# PWR_Supply.net
KiCad netlist of a schematic drawn in Altium Designer
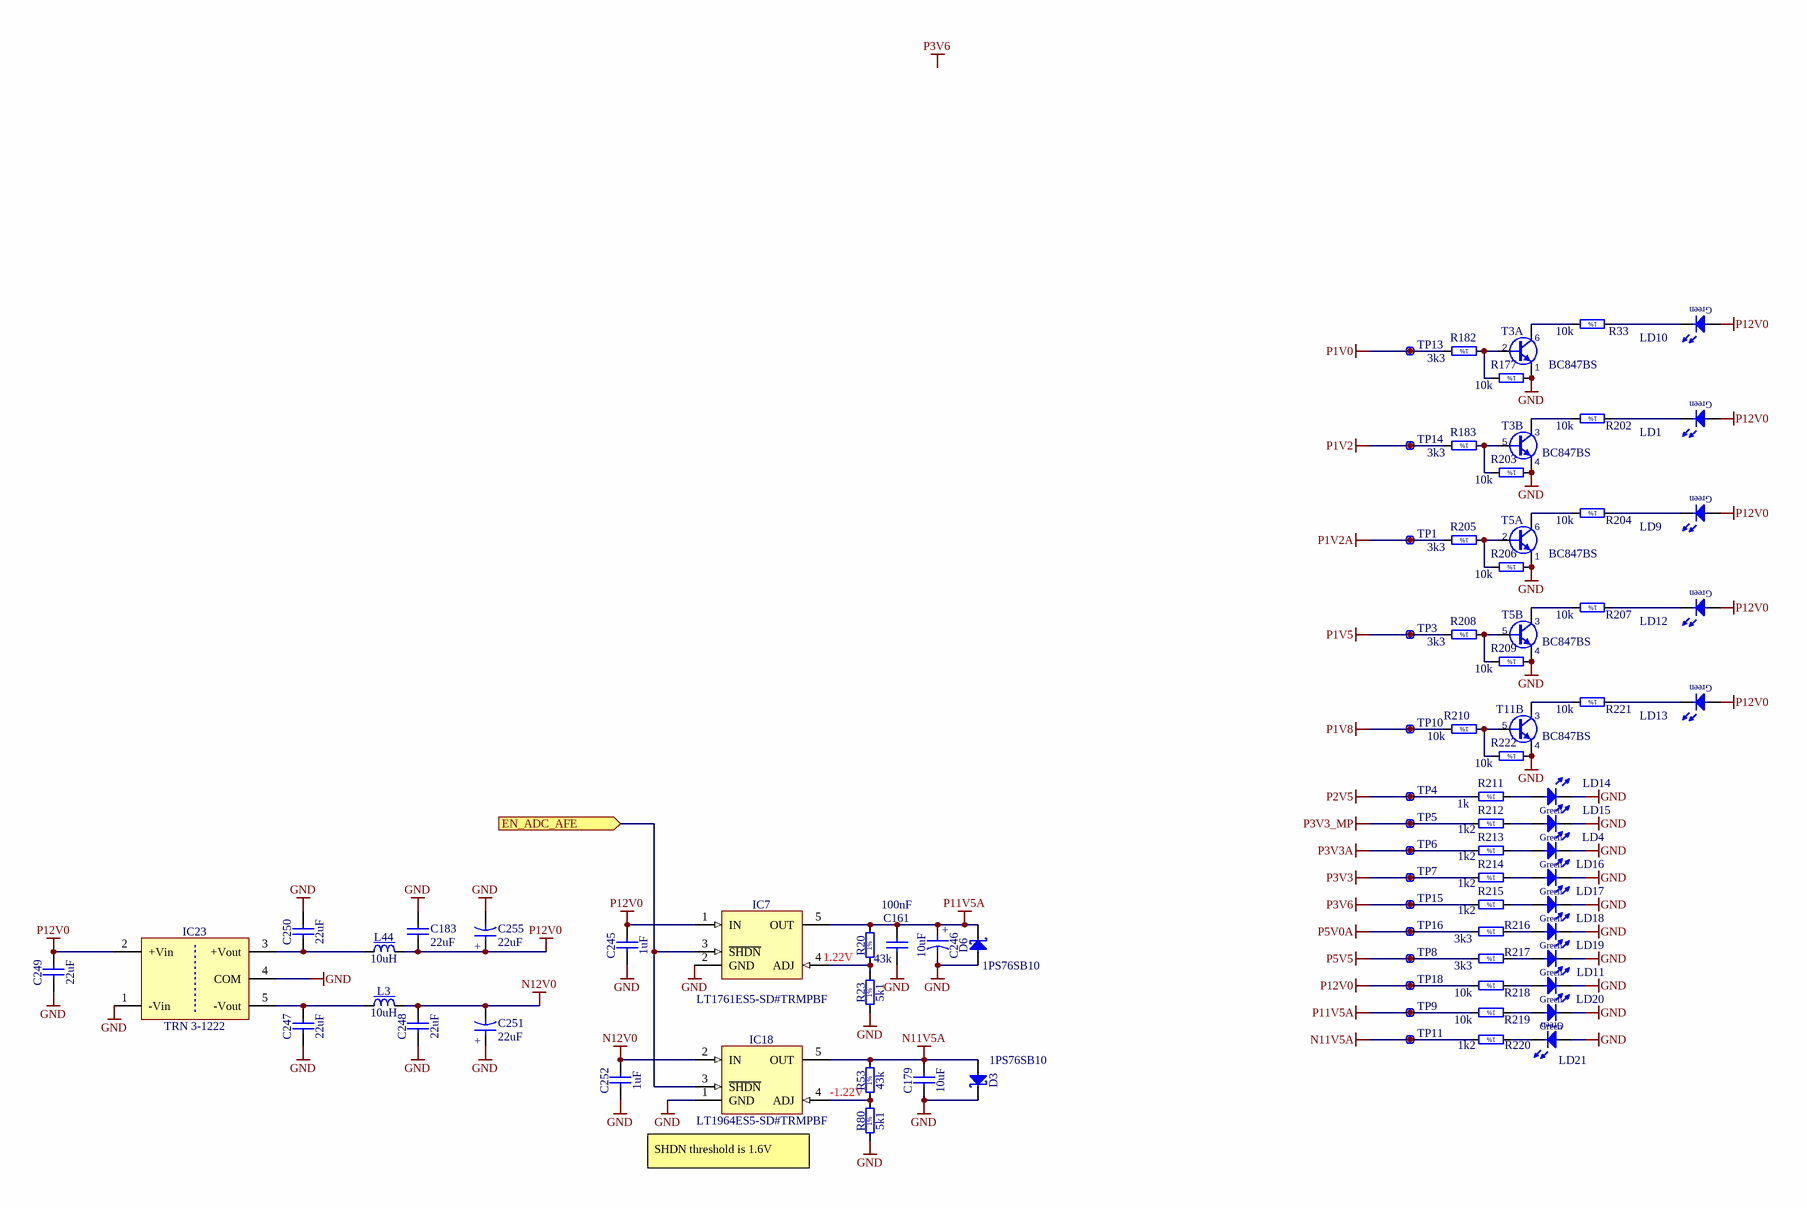
[diagram p0: PWR_Supply.SchDoc]

(export (version "E")
  (design (tool "Eeschema 10.0.6"))
  (components
    (comp (ref "C161")
      (value "100nF")
      (footprint "CAPC1005X55N")
      (description "Non-polarised capacitor")
      (fields
        (field (name "PART NUMBER") "CC0402_100NF_16V_10%_X5R")
        (field (name "VOLTAGE") "16V")
        (field (name "AUTHOR") "CERN DEM JLC")
      )
      (libsource (lib "Capacitors") (part "Capacitor - non polarized"))
    )
    (comp (ref "C179")
      (value "10uF")
      (footprint "CAPC2012X135N")
      (description "Non-polarised capacitor")
      (fields
        (field (name "PART NUMBER") "CC0805_10UF_16V_10%_X5R")
        (field (name "VOLTAGE") "16V")
        (field (name "AUTHOR") "CERN DEM JLC")
      )
      (libsource (lib "Capacitors") (part "Capacitor - non polarized"))
    )
    (comp (ref "C183")
      (value "22uF")
      (footprint "CAPC2012X135N")
      (description "Non-polarised capacitor")
      (fields
        (field (name "PART NUMBER") "CC0805_22UF_16V_10%_X5R")
        (field (name "VOLTAGE") "16V")
        (field (name "AUTHOR") "CERN DEM JLC")
      )
      (libsource (lib "Capacitors") (part "Capacitor - non polarized"))
    )
    (comp (ref "C245")
      (value "1uF")
      (footprint "CAPC1608X87N")
      (description "Non-polarised capacitor")
      (fields
        (field (name "PART NUMBER") "CC0603_1UF_25V_10%_X7R")
        (field (name "VOLTAGE") "25V")
        (field (name "AUTHOR") "CERN DEM JLC")
      )
      (libsource (lib "Capacitors") (part "Capacitor - non polarized"))
    )
    (comp (ref "C246")
      (value "10uF")
      (footprint "CAPMP3216X180N")
      (description "Polarised capacitor")
      (fields
        (field (name "PART NUMBER") "CTE3216-18_10UF_16V_20%_AVX_TCJ")
        (field (name "VOLTAGE") "16V")
        (field (name "AUTHOR") "CERN DEM JLC")
      )
      (libsource (lib "Capacitors") (part "Capacitor - polarized"))
    )
    (comp (ref "C247")
      (value "22uF")
      (footprint "CAPC2012X135N")
      (description "Non-polarised capacitor")
      (fields
        (field (name "PART NUMBER") "CC0805_22UF_16V_10%_X5R")
        (field (name "VOLTAGE") "16V")
        (field (name "AUTHOR") "CERN DEM JLC")
      )
      (libsource (lib "Capacitors") (part "Capacitor - non polarized"))
    )
    (comp (ref "C248")
      (value "22uF")
      (footprint "CAPC2012X135N")
      (description "Non-polarised capacitor")
      (fields
        (field (name "PART NUMBER") "CC0805_22UF_16V_10%_X5R")
        (field (name "VOLTAGE") "16V")
        (field (name "AUTHOR") "CERN DEM JLC")
      )
      (libsource (lib "Capacitors") (part "Capacitor - non polarized"))
    )
    (comp (ref "C249")
      (value "22uF")
      (footprint "CAPC2012X135N")
      (description "Non-polarised capacitor")
      (fields
        (field (name "PART NUMBER") "CC0805_22UF_16V_10%_X5R")
        (field (name "VOLTAGE") "16V")
        (field (name "AUTHOR") "CERN DEM JLC")
      )
      (libsource (lib "Capacitors") (part "Capacitor - non polarized"))
    )
    (comp (ref "C250")
      (value "22uF")
      (footprint "CAPC2012X135N")
      (description "Non-polarised capacitor")
      (fields
        (field (name "PART NUMBER") "CC0805_22UF_16V_10%_X5R")
        (field (name "VOLTAGE") "16V")
        (field (name "AUTHOR") "CERN DEM JLC")
      )
      (libsource (lib "Capacitors") (part "Capacitor - non polarized"))
    )
    (comp (ref "C251")
      (value "22uF")
      (footprint "CAPMP3528X210N")
      (description "Polarised capacitor")
      (fields
        (field (name "PART NUMBER") "CTE3528-21_22UF_10V_10%_LESR0700")
        (field (name "VOLTAGE") "10V")
        (field (name "AUTHOR") "CERN DEM JLC")
      )
      (libsource (lib "Capacitors") (part "Capacitor - polarized"))
    )
    (comp (ref "C252")
      (value "1uF")
      (footprint "CAPC1608X87N")
      (description "Non-polarised capacitor")
      (fields
        (field (name "PART NUMBER") "CC0603_1UF_25V_10%_X7R")
        (field (name "VOLTAGE") "25V")
        (field (name "AUTHOR") "CERN DEM JLC")
      )
      (libsource (lib "Capacitors") (part "Capacitor - non polarized"))
    )
    (comp (ref "C255")
      (value "22uF")
      (footprint "CAPMP3528X210N")
      (description "Polarised capacitor")
      (fields
        (field (name "PART NUMBER") "CTE3528-21_22UF_10V_10%_LESR0700")
        (field (name "VOLTAGE") "10V")
        (field (name "AUTHOR") "CERN DEM JLC")
      )
      (libsource (lib "Capacitors") (part "Capacitor - polarized"))
    )
    (comp (ref "D3")
      (value "1PS76SB10")
      (footprint "SOD2512X110N")
      (description "Schottky Diode")
      (fields
        (field (name "VOLTAGE") "30V")
        (field (name "POWER") "200mA")
        (field (name "AUTHOR") "CERN DEM JLC")
      )
      (libsource (lib "ICs And Semiconductors") (part "Diode Schottky"))
    )
    (comp (ref "D6")
      (value "1PS76SB10")
      (footprint "SOD2512X110N")
      (description "Schottky Diode")
      (fields
        (field (name "VOLTAGE") "30V")
        (field (name "POWER") "200mA")
        (field (name "AUTHOR") "CERN DEM JLC")
      )
      (libsource (lib "ICs And Semiconductors") (part "Diode Schottky"))
    )
    (comp (ref "IC7")
      (value "LT1761ES5-SD#TRMPBF")
      (footprint "SOT95P280X100-5N")
      (description "100mA, Low Noise, LDO Micropower Adjustable Regulator in SOT-23")
      (fields (field (name "MANUFACTURER") "LINEAR TECHNOLOGY") (field (name "AUTHOR") "CERN DEM JLC"))
      (libsource (lib "ICs And Semiconductors") (part "LT1761-SD"))
    )
    (comp (ref "IC18")
      (value "LT1964ES5-SD#TRMPBF")
      (footprint "SOT95P280X100-5N")
      (description "200mA, Low Noise, Low Dropout Negative Micropower Regulator")
      (fields (field (name "MANUFACTURER") "LINEAR TECHNOLOGY") (field (name "AUTHOR") "CERN DEM JLC"))
      (libsource (lib "ICs And Semiconductors") (part "LT1964-SD"))
    )
    (comp (ref "IC23")
      (value "TRN 3-1222")
      (footprint "DCDC_TRACO_TRN3")
      (description "TRACO, TRN 3 Serie, Dual Output DCDC Converter")
      (fields (field (name "MANUFACTURER") "TRACO POWER") (field (name "AUTHOR") "CERN DEM JLC"))
      (libsource (lib "ICs And Semiconductors") (part "DCDC_TRACO_TRN3_Dual Output"))
    )
    (comp (ref "L3")
      (value "10uH")
      (footprint "IND_MURATA-PS_8400")
      (description "Inductor With Core")
      (fields
        (field (name "PART NUMBER") "IND_10UH_10%_MURATA-PS_8400")
        (field (name "POWER") "950mA")
        (field (name "AUTHOR") "CERN DEM JLC")
      )
      (libsource (lib "Inductors & Transformers") (part "Inductor With Magnetic core"))
    )
    (comp (ref "L44")
      (value "10uH")
      (footprint "IND_MURATA-PS_8400")
      (description "Inductor With Core")
      (fields
        (field (name "PART NUMBER") "IND_10UH_10%_MURATA-PS_8400")
        (field (name "POWER") "950mA")
        (field (name "AUTHOR") "CERN DEM JLC")
      )
      (libsource (lib "Inductors & Transformers") (part "Inductor With Magnetic core"))
    )
    (comp (ref "LD1")
      (value "Green")
      (footprint "LED_KINGBRIGHT_KPH-1608CGCKr")
      (description "Green 0603")
      (fields
        (field (name "PART NUMBER") "LED_KINGBRIGHT_KPH-1608CGCK")
        (field (name "MANUFACTURER") "KINGBRIGHT")
        (field (name "AUTHOR") "CERN DEM JLC")
      )
      (libsource (lib "LIBRARY_SCH") (part "LED_0603_Green"))
    )
    (comp (ref "LD4")
      (value "Green")
      (footprint "LED_KINGBRIGHT_KPH-1608CGCKr")
      (description "Green 0603")
      (fields
        (field (name "PART NUMBER") "LED_KINGBRIGHT_KPH-1608CGCK")
        (field (name "MANUFACTURER") "KINGBRIGHT")
        (field (name "AUTHOR") "CERN DEM JLC")
      )
      (libsource (lib "LIBRARY_SCH") (part "LED_0603_Green"))
    )
    (comp (ref "LD9")
      (value "Green")
      (footprint "LED_KINGBRIGHT_KPH-1608CGCKr")
      (description "Green 0603")
      (fields
        (field (name "PART NUMBER") "LED_KINGBRIGHT_KPH-1608CGCK")
        (field (name "MANUFACTURER") "KINGBRIGHT")
        (field (name "AUTHOR") "CERN DEM JLC")
      )
      (libsource (lib "LIBRARY_SCH") (part "LED_0603_Green"))
    )
    (comp (ref "LD10")
      (value "Green")
      (footprint "LED_KINGBRIGHT_KPH-1608CGCKr")
      (description "Green 0603")
      (fields
        (field (name "PART NUMBER") "LED_KINGBRIGHT_KPH-1608CGCK")
        (field (name "MANUFACTURER") "KINGBRIGHT")
        (field (name "AUTHOR") "CERN DEM JLC")
      )
      (libsource (lib "LIBRARY_SCH") (part "LED_0603_Green"))
    )
    (comp (ref "LD11")
      (value "Green")
      (footprint "LED_KINGBRIGHT_KPH-1608CGCKr")
      (description "Green 0603")
      (fields
        (field (name "PART NUMBER") "LED_KINGBRIGHT_KPH-1608CGCK")
        (field (name "MANUFACTURER") "KINGBRIGHT")
        (field (name "AUTHOR") "CERN DEM JLC")
      )
      (libsource (lib "LIBRARY_SCH") (part "LED_0603_Green"))
    )
    (comp (ref "LD12")
      (value "Green")
      (footprint "LED_KINGBRIGHT_KPH-1608CGCKr")
      (description "Green 0603")
      (fields
        (field (name "PART NUMBER") "LED_KINGBRIGHT_KPH-1608CGCK")
        (field (name "MANUFACTURER") "KINGBRIGHT")
        (field (name "AUTHOR") "CERN DEM JLC")
      )
      (libsource (lib "LIBRARY_SCH") (part "LED_0603_Green"))
    )
    (comp (ref "LD13")
      (value "Green")
      (footprint "LED_KINGBRIGHT_KPH-1608CGCKr")
      (description "Green 0603")
      (fields
        (field (name "PART NUMBER") "LED_KINGBRIGHT_KPH-1608CGCK")
        (field (name "MANUFACTURER") "KINGBRIGHT")
        (field (name "AUTHOR") "CERN DEM JLC")
      )
      (libsource (lib "LIBRARY_SCH") (part "LED_0603_Green"))
    )
    (comp (ref "LD14")
      (value "Green")
      (footprint "LED_KINGBRIGHT_KPH-1608CGCKr")
      (description "Green 0603")
      (fields
        (field (name "PART NUMBER") "LED_KINGBRIGHT_KPH-1608CGCK")
        (field (name "MANUFACTURER") "KINGBRIGHT")
        (field (name "AUTHOR") "CERN DEM JLC")
      )
      (libsource (lib "LIBRARY_SCH") (part "LED_0603_Green"))
    )
    (comp (ref "LD15")
      (value "Green")
      (footprint "LED_KINGBRIGHT_KPH-1608CGCKr")
      (description "Green 0603")
      (fields
        (field (name "PART NUMBER") "LED_KINGBRIGHT_KPH-1608CGCK")
        (field (name "MANUFACTURER") "KINGBRIGHT")
        (field (name "AUTHOR") "CERN DEM JLC")
      )
      (libsource (lib "LIBRARY_SCH") (part "LED_0603_Green"))
    )
    (comp (ref "LD16")
      (value "Green")
      (footprint "LED_KINGBRIGHT_KPH-1608CGCKr")
      (description "Green 0603")
      (fields
        (field (name "PART NUMBER") "LED_KINGBRIGHT_KPH-1608CGCK")
        (field (name "MANUFACTURER") "KINGBRIGHT")
        (field (name "AUTHOR") "CERN DEM JLC")
      )
      (libsource (lib "LIBRARY_SCH") (part "LED_0603_Green"))
    )
    (comp (ref "LD17")
      (value "Green")
      (footprint "LED_KINGBRIGHT_KPH-1608CGCKr")
      (description "Green 0603")
      (fields
        (field (name "PART NUMBER") "LED_KINGBRIGHT_KPH-1608CGCK")
        (field (name "MANUFACTURER") "KINGBRIGHT")
        (field (name "AUTHOR") "CERN DEM JLC")
      )
      (libsource (lib "LIBRARY_SCH") (part "LED_0603_Green"))
    )
    (comp (ref "LD18")
      (value "Green")
      (footprint "LED_KINGBRIGHT_KPH-1608CGCKr")
      (description "Green 0603")
      (fields
        (field (name "PART NUMBER") "LED_KINGBRIGHT_KPH-1608CGCK")
        (field (name "MANUFACTURER") "KINGBRIGHT")
        (field (name "AUTHOR") "CERN DEM JLC")
      )
      (libsource (lib "LIBRARY_SCH") (part "LED_0603_Green"))
    )
    (comp (ref "LD19")
      (value "Green")
      (footprint "LED_KINGBRIGHT_KPH-1608CGCKr")
      (description "Green 0603")
      (fields
        (field (name "PART NUMBER") "LED_KINGBRIGHT_KPH-1608CGCK")
        (field (name "MANUFACTURER") "KINGBRIGHT")
        (field (name "AUTHOR") "CERN DEM JLC")
      )
      (libsource (lib "LIBRARY_SCH") (part "LED_0603_Green"))
    )
    (comp (ref "LD20")
      (value "Green")
      (footprint "LED_KINGBRIGHT_KPH-1608CGCKr")
      (description "Green 0603")
      (fields
        (field (name "PART NUMBER") "LED_KINGBRIGHT_KPH-1608CGCK")
        (field (name "MANUFACTURER") "KINGBRIGHT")
        (field (name "AUTHOR") "CERN DEM JLC")
      )
      (libsource (lib "LIBRARY_SCH") (part "LED_0603_Green"))
    )
    (comp (ref "LD21")
      (value "Green")
      (footprint "LED_KINGBRIGHT_KPH-1608CGCKr")
      (description "Green 0603")
      (fields
        (field (name "PART NUMBER") "LED_KINGBRIGHT_KPH-1608CGCK")
        (field (name "MANUFACTURER") "KINGBRIGHT")
        (field (name "AUTHOR") "CERN DEM JLC")
      )
      (libsource (lib "LIBRARY_SCH") (part "LED_0603_Green"))
    )
    (comp (ref "R20")
      (value "43k")
      (footprint "RESC1005X40N")
      (description "Resistor - 1%")
      (fields
        (field (name "PART NUMBER") "R0402_43K_1%_0.0625W_100PPM")
        (field (name "POWER") "0.0625W")
        (field (name "AUTHOR") "CERN DEM JLC")
      )
      (libsource (lib "Resistors") (part "Resistor - 1%"))
    )
    (comp (ref "R23")
      (value "5k1")
      (footprint "RESC1005X40N")
      (description "Resistor - 1%")
      (fields
        (field (name "PART NUMBER") "R0402_5K1_1%_0.0625W_100PPM")
        (field (name "POWER") "0.0625W")
        (field (name "AUTHOR") "CERN DEM JLC")
      )
      (libsource (lib "Resistors") (part "Resistor - 1%"))
    )
    (comp (ref "R33")
      (value "10k")
      (footprint "RESC1005X40N")
      (description "Resistor - 1%")
      (fields
        (field (name "PART NUMBER") "R0402_10K_1%_0.0625W_100PPM")
        (field (name "POWER") "0.0625W")
        (field (name "AUTHOR") "CERN DEM JLC")
      )
      (libsource (lib "Resistors") (part "Resistor - 1%"))
    )
    (comp (ref "R53")
      (value "43k")
      (footprint "RESC1005X40N")
      (description "Resistor - 1%")
      (fields
        (field (name "PART NUMBER") "R0402_43K_1%_0.0625W_100PPM")
        (field (name "POWER") "0.0625W")
        (field (name "AUTHOR") "CERN DEM JLC")
      )
      (libsource (lib "Resistors") (part "Resistor - 1%"))
    )
    (comp (ref "R80")
      (value "5k1")
      (footprint "RESC1005X40N")
      (description "Resistor - 1%")
      (fields
        (field (name "PART NUMBER") "R0402_5K1_1%_0.0625W_100PPM")
        (field (name "POWER") "0.0625W")
        (field (name "AUTHOR") "CERN DEM JLC")
      )
      (libsource (lib "Resistors") (part "Resistor - 1%"))
    )
    (comp (ref "R177")
      (value "10k")
      (footprint "RESC1005X40N")
      (description "Resistor - 1%")
      (fields
        (field (name "PART NUMBER") "R0402_10K_1%_0.0625W_100PPM")
        (field (name "POWER") "0.0625W")
        (field (name "AUTHOR") "CERN DEM JLC")
      )
      (libsource (lib "Resistors") (part "Resistor - 1%"))
    )
    (comp (ref "R182")
      (value "3k3")
      (footprint "RESC1608X55N")
      (description "Resistor - 1%")
      (fields
        (field (name "PART NUMBER") "R0603_3K3_1%_0.1W_100PPM")
        (field (name "POWER") "0.1W")
        (field (name "AUTHOR") "CERN DEM JLC")
      )
      (libsource (lib "Resistors") (part "Resistor - 1%"))
    )
    (comp (ref "R183")
      (value "3k3")
      (footprint "RESC1608X55N")
      (description "Resistor - 1%")
      (fields
        (field (name "PART NUMBER") "R0603_3K3_1%_0.1W_100PPM")
        (field (name "POWER") "0.1W")
        (field (name "AUTHOR") "CERN DEM JLC")
      )
      (libsource (lib "Resistors") (part "Resistor - 1%"))
    )
    (comp (ref "R202")
      (value "10k")
      (footprint "RESC1005X40N")
      (description "Resistor - 1%")
      (fields
        (field (name "PART NUMBER") "R0402_10K_1%_0.0625W_100PPM")
        (field (name "POWER") "0.0625W")
        (field (name "AUTHOR") "CERN DEM JLC")
      )
      (libsource (lib "Resistors") (part "Resistor - 1%"))
    )
    (comp (ref "R203")
      (value "10k")
      (footprint "RESC1005X40N")
      (description "Resistor - 1%")
      (fields
        (field (name "PART NUMBER") "R0402_10K_1%_0.0625W_100PPM")
        (field (name "POWER") "0.0625W")
        (field (name "AUTHOR") "CERN DEM JLC")
      )
      (libsource (lib "Resistors") (part "Resistor - 1%"))
    )
    (comp (ref "R204")
      (value "10k")
      (footprint "RESC1005X40N")
      (description "Resistor - 1%")
      (fields
        (field (name "PART NUMBER") "R0402_10K_1%_0.0625W_100PPM")
        (field (name "POWER") "0.0625W")
        (field (name "AUTHOR") "CERN DEM JLC")
      )
      (libsource (lib "Resistors") (part "Resistor - 1%"))
    )
    (comp (ref "R205")
      (value "3k3")
      (footprint "RESC1608X55N")
      (description "Resistor - 1%")
      (fields
        (field (name "PART NUMBER") "R0603_3K3_1%_0.1W_100PPM")
        (field (name "POWER") "0.1W")
        (field (name "AUTHOR") "CERN DEM JLC")
      )
      (libsource (lib "Resistors") (part "Resistor - 1%"))
    )
    (comp (ref "R206")
      (value "10k")
      (footprint "RESC1005X40N")
      (description "Resistor - 1%")
      (fields
        (field (name "PART NUMBER") "R0402_10K_1%_0.0625W_100PPM")
        (field (name "POWER") "0.0625W")
        (field (name "AUTHOR") "CERN DEM JLC")
      )
      (libsource (lib "Resistors") (part "Resistor - 1%"))
    )
    (comp (ref "R207")
      (value "10k")
      (footprint "RESC1005X40N")
      (description "Resistor - 1%")
      (fields
        (field (name "PART NUMBER") "R0402_10K_1%_0.0625W_100PPM")
        (field (name "POWER") "0.0625W")
        (field (name "AUTHOR") "CERN DEM JLC")
      )
      (libsource (lib "Resistors") (part "Resistor - 1%"))
    )
    (comp (ref "R208")
      (value "3k3")
      (footprint "RESC1608X55N")
      (description "Resistor - 1%")
      (fields
        (field (name "PART NUMBER") "R0603_3K3_1%_0.1W_100PPM")
        (field (name "POWER") "0.1W")
        (field (name "AUTHOR") "CERN DEM JLC")
      )
      (libsource (lib "Resistors") (part "Resistor - 1%"))
    )
    (comp (ref "R209")
      (value "10k")
      (footprint "RESC1005X40N")
      (description "Resistor - 1%")
      (fields
        (field (name "PART NUMBER") "R0402_10K_1%_0.0625W_100PPM")
        (field (name "POWER") "0.0625W")
        (field (name "AUTHOR") "CERN DEM JLC")
      )
      (libsource (lib "Resistors") (part "Resistor - 1%"))
    )
    (comp (ref "R210")
      (value "10k")
      (footprint "RESC1005X40N")
      (description "Resistor - 1%")
      (fields
        (field (name "PART NUMBER") "R0402_10K_1%_0.0625W_100PPM")
        (field (name "POWER") "0.0625W")
        (field (name "AUTHOR") "CERN DEM JLC")
      )
      (libsource (lib "Resistors") (part "Resistor - 1%"))
    )
    (comp (ref "R211")
      (value "1k")
      (footprint "RESC1608X55N")
      (description "Resistor - 1%")
      (fields
        (field (name "PART NUMBER") "R0603_1K_1%_0.1W_100PPM")
        (field (name "POWER") "0.1W")
        (field (name "AUTHOR") "CERN DEM JLC")
      )
      (libsource (lib "Resistors") (part "Resistor - 1%"))
    )
    (comp (ref "R212")
      (value "1k2")
      (footprint "RESC1608X55N")
      (description "Resistor - 1%")
      (fields
        (field (name "PART NUMBER") "R0603_1K2_1%_0.1W_100PPM")
        (field (name "POWER") "0.1W")
        (field (name "AUTHOR") "CERN DEM JLC")
      )
      (libsource (lib "Resistors") (part "Resistor - 1%"))
    )
    (comp (ref "R213")
      (value "1k2")
      (footprint "RESC1608X55N")
      (description "Resistor - 1%")
      (fields
        (field (name "PART NUMBER") "R0603_1K2_1%_0.1W_100PPM")
        (field (name "POWER") "0.1W")
        (field (name "AUTHOR") "CERN DEM JLC")
      )
      (libsource (lib "Resistors") (part "Resistor - 1%"))
    )
    (comp (ref "R214")
      (value "1k2")
      (footprint "RESC1608X55N")
      (description "Resistor - 1%")
      (fields
        (field (name "PART NUMBER") "R0603_1K2_1%_0.1W_100PPM")
        (field (name "POWER") "0.1W")
        (field (name "AUTHOR") "CERN DEM JLC")
      )
      (libsource (lib "Resistors") (part "Resistor - 1%"))
    )
    (comp (ref "R215")
      (value "1k2")
      (footprint "RESC1608X55N")
      (description "Resistor - 1%")
      (fields
        (field (name "PART NUMBER") "R0603_1K2_1%_0.1W_100PPM")
        (field (name "POWER") "0.1W")
        (field (name "AUTHOR") "CERN DEM JLC")
      )
      (libsource (lib "Resistors") (part "Resistor - 1%"))
    )
    (comp (ref "R216")
      (value "3k3")
      (footprint "RESC1608X55N")
      (description "Resistor - 1%")
      (fields
        (field (name "PART NUMBER") "R0603_3K3_1%_0.1W_100PPM")
        (field (name "POWER") "0.1W")
        (field (name "AUTHOR") "CERN DEM JLC")
      )
      (libsource (lib "Resistors") (part "Resistor - 1%"))
    )
    (comp (ref "R217")
      (value "3k3")
      (footprint "RESC1608X55N")
      (description "Resistor - 1%")
      (fields
        (field (name "PART NUMBER") "R0603_3K3_1%_0.1W_100PPM")
        (field (name "POWER") "0.1W")
        (field (name "AUTHOR") "CERN DEM JLC")
      )
      (libsource (lib "Resistors") (part "Resistor - 1%"))
    )
    (comp (ref "R218")
      (value "10k")
      (footprint "RESC1005X40N")
      (description "Resistor - 1%")
      (fields
        (field (name "PART NUMBER") "R0402_10K_1%_0.0625W_100PPM")
        (field (name "POWER") "0.0625W")
        (field (name "AUTHOR") "CERN DEM JLC")
      )
      (libsource (lib "Resistors") (part "Resistor - 1%"))
    )
    (comp (ref "R219")
      (value "10k")
      (footprint "RESC1005X40N")
      (description "Resistor - 1%")
      (fields
        (field (name "PART NUMBER") "R0402_10K_1%_0.0625W_100PPM")
        (field (name "POWER") "0.0625W")
        (field (name "AUTHOR") "CERN DEM JLC")
      )
      (libsource (lib "Resistors") (part "Resistor - 1%"))
    )
    (comp (ref "R220")
      (value "1k2")
      (footprint "RESC1608X55N")
      (description "Resistor - 1%")
      (fields
        (field (name "PART NUMBER") "R0603_1K2_1%_0.1W_100PPM")
        (field (name "POWER") "0.1W")
        (field (name "AUTHOR") "CERN DEM JLC")
      )
      (libsource (lib "Resistors") (part "Resistor - 1%"))
    )
    (comp (ref "R221")
      (value "10k")
      (footprint "RESC1005X40N")
      (description "Resistor - 1%")
      (fields
        (field (name "PART NUMBER") "R0402_10K_1%_0.0625W_100PPM")
        (field (name "POWER") "0.0625W")
        (field (name "AUTHOR") "CERN DEM JLC")
      )
      (libsource (lib "Resistors") (part "Resistor - 1%"))
    )
    (comp (ref "R222")
      (value "10k")
      (footprint "RESC1005X40N")
      (description "Resistor - 1%")
      (fields
        (field (name "PART NUMBER") "R0402_10K_1%_0.0625W_100PPM")
        (field (name "POWER") "0.0625W")
        (field (name "AUTHOR") "CERN DEM JLC")
      )
      (libsource (lib "Resistors") (part "Resistor - 1%"))
    )
    (comp (ref "T3")
      (value "BC847BS")
      (footprint "SOT65P210X110-6N")
      (description "45V 100mA Dual NPN General-Purpose Transistor")
      (fields (field (name "MANUFACTURER") "NXP SEMICONDUCTORS") (field (name "AUTHOR") "CERN DEM JMW"))
      (libsource (lib "ICs And Semiconductors") (part "BC847BS"))
    )
    (comp (ref "T5")
      (value "BC847BS")
      (footprint "SOT65P210X110-6N")
      (description "45V 100mA Dual NPN General-Purpose Transistor")
      (fields (field (name "MANUFACTURER") "NXP SEMICONDUCTORS") (field (name "AUTHOR") "CERN DEM JMW"))
      (libsource (lib "ICs And Semiconductors") (part "BC847BS"))
    )
    (comp (ref "T11")
      (value "BC847BS")
      (footprint "SOT65P210X110-6N")
      (description "45V 100mA Dual NPN General-Purpose Transistor")
      (fields (field (name "MANUFACTURER") "NXP SEMICONDUCTORS") (field (name "AUTHOR") "CERN DEM JMW"))
      (libsource (lib "ICs And Semiconductors") (part "BC847BS"))
    )
    (comp (ref "TP1")
      (value "Test Point")
      (footprint "TPS127")
      (fields (field (name "PART NUMBER") "SMD_PAD_1.27X1.27MM") (field (name "AUTHOR") "CERN DEM JLC"))
      (libsource (lib "Eletro-mechanical") (part "Test Point"))
    )
    (comp (ref "TP3")
      (value "Test Point")
      (footprint "TPS127")
      (fields (field (name "PART NUMBER") "SMD_PAD_1.27X1.27MM") (field (name "AUTHOR") "CERN DEM JLC"))
      (libsource (lib "Eletro-mechanical") (part "Test Point"))
    )
    (comp (ref "TP4")
      (value "Test Point")
      (footprint "TPS127")
      (fields (field (name "PART NUMBER") "SMD_PAD_1.27X1.27MM") (field (name "AUTHOR") "CERN DEM JLC"))
      (libsource (lib "Eletro-mechanical") (part "Test Point"))
    )
    (comp (ref "TP5")
      (value "Test Point")
      (footprint "TPS127")
      (fields (field (name "PART NUMBER") "SMD_PAD_1.27X1.27MM") (field (name "AUTHOR") "CERN DEM JLC"))
      (libsource (lib "Eletro-mechanical") (part "Test Point"))
    )
    (comp (ref "TP6")
      (value "Test Point")
      (footprint "TPS127")
      (fields (field (name "PART NUMBER") "SMD_PAD_1.27X1.27MM") (field (name "AUTHOR") "CERN DEM JLC"))
      (libsource (lib "Eletro-mechanical") (part "Test Point"))
    )
    (comp (ref "TP7")
      (value "Test Point")
      (footprint "TPS127")
      (fields (field (name "PART NUMBER") "SMD_PAD_1.27X1.27MM") (field (name "AUTHOR") "CERN DEM JLC"))
      (libsource (lib "Eletro-mechanical") (part "Test Point"))
    )
    (comp (ref "TP8")
      (value "Test Point")
      (footprint "TPS127")
      (fields (field (name "PART NUMBER") "SMD_PAD_1.27X1.27MM") (field (name "AUTHOR") "CERN DEM JLC"))
      (libsource (lib "Eletro-mechanical") (part "Test Point"))
    )
    (comp (ref "TP9")
      (value "Test Point")
      (footprint "TPS127")
      (fields (field (name "PART NUMBER") "SMD_PAD_1.27X1.27MM") (field (name "AUTHOR") "CERN DEM JLC"))
      (libsource (lib "Eletro-mechanical") (part "Test Point"))
    )
    (comp (ref "TP10")
      (value "Test Point")
      (footprint "TPS127")
      (fields (field (name "PART NUMBER") "SMD_PAD_1.27X1.27MM") (field (name "AUTHOR") "CERN DEM JLC"))
      (libsource (lib "Eletro-mechanical") (part "Test Point"))
    )
    (comp (ref "TP11")
      (value "Test Point")
      (footprint "TPS127")
      (fields (field (name "PART NUMBER") "SMD_PAD_1.27X1.27MM") (field (name "AUTHOR") "CERN DEM JLC"))
      (libsource (lib "Eletro-mechanical") (part "Test Point"))
    )
    (comp (ref "TP13")
      (value "Test Point")
      (footprint "TPS127")
      (fields (field (name "PART NUMBER") "SMD_PAD_1.27X1.27MM") (field (name "AUTHOR") "CERN DEM JLC"))
      (libsource (lib "Eletro-mechanical") (part "Test Point"))
    )
    (comp (ref "TP14")
      (value "Test Point")
      (footprint "TPS127")
      (fields (field (name "PART NUMBER") "SMD_PAD_1.27X1.27MM") (field (name "AUTHOR") "CERN DEM JLC"))
      (libsource (lib "Eletro-mechanical") (part "Test Point"))
    )
    (comp (ref "TP15")
      (value "Test Point")
      (footprint "TPS127")
      (fields (field (name "PART NUMBER") "SMD_PAD_1.27X1.27MM") (field (name "AUTHOR") "CERN DEM JLC"))
      (libsource (lib "Eletro-mechanical") (part "Test Point"))
    )
    (comp (ref "TP16")
      (value "Test Point")
      (footprint "TPS127")
      (fields (field (name "PART NUMBER") "SMD_PAD_1.27X1.27MM") (field (name "AUTHOR") "CERN DEM JLC"))
      (libsource (lib "Eletro-mechanical") (part "Test Point"))
    )
    (comp (ref "TP18")
      (value "Test Point")
      (footprint "TPS127")
      (fields (field (name "PART NUMBER") "SMD_PAD_1.27X1.27MM") (field (name "AUTHOR") "CERN DEM JLC"))
      (libsource (lib "Eletro-mechanical") (part "Test Point"))
    )
  )
  (nets
    (net (code "1") (name "/EN_ADC_AFE") (class "Default")
      (node (ref "IC18") (pin "3") (pinfunction "~{SHDN}_3") (pintype "input"))
      (node (ref "IC7") (pin "3") (pinfunction "~{SHDN}_3") (pintype "input"))
    )
    (net (code "2") (name "GND") (class "Default")
      (node (ref "C161") (pin "1") (pinfunction "1_1") (pintype "passive"))
      (node (ref "C179") (pin "1") (pinfunction "1_1") (pintype "passive"))
      (node (ref "C183") (pin "1") (pinfunction "1_1") (pintype "passive"))
      (node (ref "C245") (pin "1") (pinfunction "1_1") (pintype "passive"))
      (node (ref "C246") (pin "2") (pinfunction "2_2") (pintype "passive"))
      (node (ref "C247") (pin "1") (pinfunction "1_1") (pintype "passive"))
      (node (ref "C248") (pin "1") (pinfunction "1_1") (pintype "passive"))
      (node (ref "C249") (pin "1") (pinfunction "1_1") (pintype "passive"))
      (node (ref "C250") (pin "2") (pinfunction "2_2") (pintype "passive"))
      (node (ref "C251") (pin "1") (pinfunction "1_1") (pintype "passive"))
      (node (ref "C252") (pin "1") (pinfunction "1_1") (pintype "passive"))
      (node (ref "C255") (pin "2") (pinfunction "2_2") (pintype "passive"))
      (node (ref "D3") (pin "1") (pinfunction "C_1") (pintype "passive"))
      (node (ref "D6") (pin "2") (pinfunction "A_2") (pintype "passive"))
      (node (ref "IC18") (pin "1") (pinfunction "GND_1") (pintype "power_in"))
      (node (ref "IC23") (pin "1") (pinfunction "-Vin_1") (pintype "power_in"))
      (node (ref "IC23") (pin "4") (pinfunction "COM_4") (pintype "power_in"))
      (node (ref "IC7") (pin "2") (pinfunction "GND_2") (pintype "power_in"))
      (node (ref "LD11") (pin "1") (pinfunction "C_1") (pintype "passive"))
      (node (ref "LD14") (pin "1") (pinfunction "C_1") (pintype "passive"))
      (node (ref "LD15") (pin "1") (pinfunction "C_1") (pintype "passive"))
      (node (ref "LD16") (pin "1") (pinfunction "C_1") (pintype "passive"))
      (node (ref "LD17") (pin "1") (pinfunction "C_1") (pintype "passive"))
      (node (ref "LD18") (pin "1") (pinfunction "C_1") (pintype "passive"))
      (node (ref "LD19") (pin "1") (pinfunction "C_1") (pintype "passive"))
      (node (ref "LD20") (pin "1") (pinfunction "C_1") (pintype "passive"))
      (node (ref "LD21") (pin "2") (pinfunction "A_2") (pintype "passive"))
      (node (ref "LD4") (pin "1") (pinfunction "C_1") (pintype "passive"))
      (node (ref "R177") (pin "1") (pinfunction "1_1") (pintype "passive"))
      (node (ref "R203") (pin "1") (pinfunction "1_1") (pintype "passive"))
      (node (ref "R206") (pin "1") (pinfunction "1_1") (pintype "passive"))
      (node (ref "R209") (pin "1") (pinfunction "1_1") (pintype "passive"))
      (node (ref "R222") (pin "1") (pinfunction "1_1") (pintype "passive"))
      (node (ref "R23") (pin "1") (pinfunction "1_1") (pintype "passive"))
      (node (ref "R80") (pin "1") (pinfunction "1_1") (pintype "passive"))
      (node (ref "T11") (pin "4") (pinfunction "E_4") (pintype "passive"))
      (node (ref "T3") (pin "1") (pinfunction "E_1") (pintype "passive"))
      (node (ref "T3") (pin "4") (pinfunction "E_4") (pintype "passive"))
      (node (ref "T5") (pin "1") (pinfunction "E_1") (pintype "passive"))
      (node (ref "T5") (pin "4") (pinfunction "E_4") (pintype "passive"))
    )
    (net (code "3") (name "N11V5A") (class "Default")
      (node (ref "C179") (pin "2") (pinfunction "2_2") (pintype "passive"))
      (node (ref "D3") (pin "2") (pinfunction "A_2") (pintype "passive"))
      (node (ref "IC18") (pin "5") (pinfunction "OUT_5") (pintype "power_in"))
      (node (ref "R220") (pin "2") (pinfunction "2_2") (pintype "passive"))
      (node (ref "R53") (pin "2") (pinfunction "2_2") (pintype "passive"))
      (node (ref "TP11") (pin "1") (pinfunction "1_1") (pintype "bidirectional"))
    )
    (net (code "4") (name "N12V0") (class "Default")
      (node (ref "C248") (pin "2") (pinfunction "2_2") (pintype "passive"))
      (node (ref "C251") (pin "2") (pinfunction "2_2") (pintype "passive"))
      (node (ref "C252") (pin "2") (pinfunction "2_2") (pintype "passive"))
      (node (ref "IC18") (pin "2") (pinfunction "IN_2") (pintype "input"))
      (node (ref "L3") (pin "2") (pinfunction "2_2") (pintype "passive"))
    )
    (net (code "5") (name "Net-(IC7-ADJ)") (class "Default")
      (node (ref "IC7") (pin "4") (pinfunction "ADJ_4") (pintype "input"))
      (node (ref "R20") (pin "1") (pinfunction "1_1") (pintype "passive"))
      (node (ref "R23") (pin "2") (pinfunction "2_2") (pintype "passive"))
    )
    (net (code "6") (name "Net-(IC18-ADJ)") (class "Default")
      (node (ref "IC18") (pin "4") (pinfunction "ADJ_4") (pintype "input"))
      (node (ref "R53") (pin "1") (pinfunction "1_1") (pintype "passive"))
      (node (ref "R80") (pin "2") (pinfunction "2_2") (pintype "passive"))
    )
    (net (code "7") (name "Net-(IC23-+Vout)") (class "Default")
      (node (ref "C250") (pin "1") (pinfunction "1_1") (pintype "passive"))
      (node (ref "IC23") (pin "3") (pinfunction "+Vout_3") (pintype "power_in"))
      (node (ref "L44") (pin "1") (pinfunction "1_1") (pintype "passive"))
    )
    (net (code "8") (name "Net-(IC23--Vout)") (class "Default")
      (node (ref "C247") (pin "2") (pinfunction "2_2") (pintype "passive"))
      (node (ref "IC23") (pin "5") (pinfunction "-Vout_5") (pintype "power_in"))
      (node (ref "L3") (pin "1") (pinfunction "1_1") (pintype "passive"))
    )
    (net (code "9") (name "Net-(LD1-C)") (class "Default")
      (node (ref "LD1") (pin "1") (pinfunction "C_1") (pintype "passive"))
      (node (ref "R202") (pin "1") (pinfunction "1_1") (pintype "passive"))
    )
    (net (code "10") (name "Net-(LD4-A)") (class "Default")
      (node (ref "LD4") (pin "2") (pinfunction "A_2") (pintype "passive"))
      (node (ref "R213") (pin "1") (pinfunction "1_1") (pintype "passive"))
    )
    (net (code "11") (name "Net-(LD9-C)") (class "Default")
      (node (ref "LD9") (pin "1") (pinfunction "C_1") (pintype "passive"))
      (node (ref "R204") (pin "1") (pinfunction "1_1") (pintype "passive"))
    )
    (net (code "12") (name "Net-(LD10-C)") (class "Default")
      (node (ref "LD10") (pin "1") (pinfunction "C_1") (pintype "passive"))
      (node (ref "R33") (pin "1") (pinfunction "1_1") (pintype "passive"))
    )
    (net (code "13") (name "Net-(LD11-A)") (class "Default")
      (node (ref "LD11") (pin "2") (pinfunction "A_2") (pintype "passive"))
      (node (ref "R218") (pin "1") (pinfunction "1_1") (pintype "passive"))
    )
    (net (code "14") (name "Net-(LD12-C)") (class "Default")
      (node (ref "LD12") (pin "1") (pinfunction "C_1") (pintype "passive"))
      (node (ref "R207") (pin "1") (pinfunction "1_1") (pintype "passive"))
    )
    (net (code "15") (name "Net-(LD13-C)") (class "Default")
      (node (ref "LD13") (pin "1") (pinfunction "C_1") (pintype "passive"))
      (node (ref "R221") (pin "1") (pinfunction "1_1") (pintype "passive"))
    )
    (net (code "16") (name "Net-(LD14-A)") (class "Default")
      (node (ref "LD14") (pin "2") (pinfunction "A_2") (pintype "passive"))
      (node (ref "R211") (pin "1") (pinfunction "1_1") (pintype "passive"))
    )
    (net (code "17") (name "Net-(LD15-A)") (class "Default")
      (node (ref "LD15") (pin "2") (pinfunction "A_2") (pintype "passive"))
      (node (ref "R212") (pin "1") (pinfunction "1_1") (pintype "passive"))
    )
    (net (code "18") (name "Net-(LD16-A)") (class "Default")
      (node (ref "LD16") (pin "2") (pinfunction "A_2") (pintype "passive"))
      (node (ref "R214") (pin "1") (pinfunction "1_1") (pintype "passive"))
    )
    (net (code "19") (name "Net-(LD17-A)") (class "Default")
      (node (ref "LD17") (pin "2") (pinfunction "A_2") (pintype "passive"))
      (node (ref "R215") (pin "1") (pinfunction "1_1") (pintype "passive"))
    )
    (net (code "20") (name "Net-(LD18-A)") (class "Default")
      (node (ref "LD18") (pin "2") (pinfunction "A_2") (pintype "passive"))
      (node (ref "R216") (pin "1") (pinfunction "1_1") (pintype "passive"))
    )
    (net (code "21") (name "Net-(LD19-A)") (class "Default")
      (node (ref "LD19") (pin "2") (pinfunction "A_2") (pintype "passive"))
      (node (ref "R217") (pin "1") (pinfunction "1_1") (pintype "passive"))
    )
    (net (code "22") (name "Net-(LD20-A)") (class "Default")
      (node (ref "LD20") (pin "2") (pinfunction "A_2") (pintype "passive"))
      (node (ref "R219") (pin "1") (pinfunction "1_1") (pintype "passive"))
    )
    (net (code "23") (name "Net-(LD21-C)") (class "Default")
      (node (ref "LD21") (pin "1") (pinfunction "C_1") (pintype "passive"))
      (node (ref "R220") (pin "1") (pinfunction "1_1") (pintype "passive"))
    )
    (net (code "24") (name "Net-(T3A-B)") (class "Default")
      (node (ref "R177") (pin "2") (pinfunction "2_2") (pintype "passive"))
      (node (ref "R182") (pin "1") (pinfunction "1_1") (pintype "passive"))
      (node (ref "T3") (pin "2") (pinfunction "B_2") (pintype "passive"))
    )
    (net (code "25") (name "Net-(T3A-C)") (class "Default")
      (node (ref "R33") (pin "2") (pinfunction "2_2") (pintype "passive"))
      (node (ref "T3") (pin "6") (pinfunction "C_6") (pintype "passive"))
    )
    (net (code "26") (name "Net-(T3B-B)") (class "Default")
      (node (ref "R183") (pin "1") (pinfunction "1_1") (pintype "passive"))
      (node (ref "R203") (pin "2") (pinfunction "2_2") (pintype "passive"))
      (node (ref "T3") (pin "5") (pinfunction "B_5") (pintype "passive"))
    )
    (net (code "27") (name "Net-(T3B-C)") (class "Default")
      (node (ref "R202") (pin "2") (pinfunction "2_2") (pintype "passive"))
      (node (ref "T3") (pin "3") (pinfunction "C_3") (pintype "passive"))
    )
    (net (code "28") (name "Net-(T5A-B)") (class "Default")
      (node (ref "R205") (pin "1") (pinfunction "1_1") (pintype "passive"))
      (node (ref "R206") (pin "2") (pinfunction "2_2") (pintype "passive"))
      (node (ref "T5") (pin "2") (pinfunction "B_2") (pintype "passive"))
    )
    (net (code "29") (name "Net-(T5A-C)") (class "Default")
      (node (ref "R204") (pin "2") (pinfunction "2_2") (pintype "passive"))
      (node (ref "T5") (pin "6") (pinfunction "C_6") (pintype "passive"))
    )
    (net (code "30") (name "Net-(T5B-B)") (class "Default")
      (node (ref "R208") (pin "1") (pinfunction "1_1") (pintype "passive"))
      (node (ref "R209") (pin "2") (pinfunction "2_2") (pintype "passive"))
      (node (ref "T5") (pin "5") (pinfunction "B_5") (pintype "passive"))
    )
    (net (code "31") (name "Net-(T5B-C)") (class "Default")
      (node (ref "R207") (pin "2") (pinfunction "2_2") (pintype "passive"))
      (node (ref "T5") (pin "3") (pinfunction "C_3") (pintype "passive"))
    )
    (net (code "32") (name "Net-(T11B-B)") (class "Default")
      (node (ref "R210") (pin "1") (pinfunction "1_1") (pintype "passive"))
      (node (ref "R222") (pin "2") (pinfunction "2_2") (pintype "passive"))
      (node (ref "T11") (pin "5") (pinfunction "B_5") (pintype "passive"))
    )
    (net (code "33") (name "Net-(T11B-C)") (class "Default")
      (node (ref "R221") (pin "2") (pinfunction "2_2") (pintype "passive"))
      (node (ref "T11") (pin "3") (pinfunction "C_3") (pintype "passive"))
    )
    (net (code "34") (name "P1V0") (class "Default")
      (node (ref "R182") (pin "2") (pinfunction "2_2") (pintype "passive"))
      (node (ref "TP13") (pin "1") (pinfunction "1_1") (pintype "bidirectional"))
    )
    (net (code "35") (name "P1V2") (class "Default")
      (node (ref "R183") (pin "2") (pinfunction "2_2") (pintype "passive"))
      (node (ref "TP14") (pin "1") (pinfunction "1_1") (pintype "bidirectional"))
    )
    (net (code "36") (name "P1V2A") (class "Default")
      (node (ref "R205") (pin "2") (pinfunction "2_2") (pintype "passive"))
      (node (ref "TP1") (pin "1") (pinfunction "1_1") (pintype "bidirectional"))
    )
    (net (code "37") (name "P1V5") (class "Default")
      (node (ref "R208") (pin "2") (pinfunction "2_2") (pintype "passive"))
      (node (ref "TP3") (pin "1") (pinfunction "1_1") (pintype "bidirectional"))
    )
    (net (code "38") (name "P1V8") (class "Default")
      (node (ref "R210") (pin "2") (pinfunction "2_2") (pintype "passive"))
      (node (ref "TP10") (pin "1") (pinfunction "1_1") (pintype "bidirectional"))
    )
    (net (code "39") (name "P2V5") (class "Default")
      (node (ref "R211") (pin "2") (pinfunction "2_2") (pintype "passive"))
      (node (ref "TP4") (pin "1") (pinfunction "1_1") (pintype "bidirectional"))
    )
    (net (code "40") (name "P3V3") (class "Default")
      (node (ref "R214") (pin "2") (pinfunction "2_2") (pintype "passive"))
      (node (ref "TP7") (pin "1") (pinfunction "1_1") (pintype "bidirectional"))
    )
    (net (code "41") (name "P3V3A") (class "Default")
      (node (ref "R213") (pin "2") (pinfunction "2_2") (pintype "passive"))
      (node (ref "TP6") (pin "1") (pinfunction "1_1") (pintype "bidirectional"))
    )
    (net (code "42") (name "P3V3_MP") (class "Default")
      (node (ref "R212") (pin "2") (pinfunction "2_2") (pintype "passive"))
      (node (ref "TP5") (pin "1") (pinfunction "1_1") (pintype "bidirectional"))
    )
    (net (code "43") (name "P3V6") (class "Default")
      (node (ref "R215") (pin "2") (pinfunction "2_2") (pintype "passive"))
      (node (ref "TP15") (pin "1") (pinfunction "1_1") (pintype "bidirectional"))
    )
    (net (code "44") (name "P5V0A") (class "Default")
      (node (ref "R216") (pin "2") (pinfunction "2_2") (pintype "passive"))
      (node (ref "TP16") (pin "1") (pinfunction "1_1") (pintype "bidirectional"))
    )
    (net (code "45") (name "P5V5") (class "Default")
      (node (ref "R217") (pin "2") (pinfunction "2_2") (pintype "passive"))
      (node (ref "TP8") (pin "1") (pinfunction "1_1") (pintype "bidirectional"))
    )
    (net (code "46") (name "P11V5A") (class "Default")
      (node (ref "C161") (pin "2") (pinfunction "2_2") (pintype "passive"))
      (node (ref "C246") (pin "1") (pinfunction "1_1") (pintype "passive"))
      (node (ref "D6") (pin "1") (pinfunction "C_1") (pintype "passive"))
      (node (ref "IC7") (pin "5") (pinfunction "OUT_5") (pintype "power_in"))
      (node (ref "R20") (pin "2") (pinfunction "2_2") (pintype "passive"))
      (node (ref "R219") (pin "2") (pinfunction "2_2") (pintype "passive"))
      (node (ref "TP9") (pin "1") (pinfunction "1_1") (pintype "bidirectional"))
    )
    (net (code "47") (name "P12V0") (class "Default")
      (node (ref "C183") (pin "2") (pinfunction "2_2") (pintype "passive"))
      (node (ref "C245") (pin "2") (pinfunction "2_2") (pintype "passive"))
      (node (ref "C249") (pin "2") (pinfunction "2_2") (pintype "passive"))
      (node (ref "C255") (pin "1") (pinfunction "1_1") (pintype "passive"))
      (node (ref "IC23") (pin "2") (pinfunction "+Vin_2") (pintype "power_in"))
      (node (ref "IC7") (pin "1") (pinfunction "IN_1") (pintype "input"))
      (node (ref "L44") (pin "2") (pinfunction "2_2") (pintype "passive"))
      (node (ref "LD1") (pin "2") (pinfunction "A_2") (pintype "passive"))
      (node (ref "LD10") (pin "2") (pinfunction "A_2") (pintype "passive"))
      (node (ref "LD12") (pin "2") (pinfunction "A_2") (pintype "passive"))
      (node (ref "LD13") (pin "2") (pinfunction "A_2") (pintype "passive"))
      (node (ref "LD9") (pin "2") (pinfunction "A_2") (pintype "passive"))
      (node (ref "R218") (pin "2") (pinfunction "2_2") (pintype "passive"))
      (node (ref "TP18") (pin "1") (pinfunction "1_1") (pintype "bidirectional"))
    )
  )
)
